# 16_LMS2_RF2_Misc.net
KiCad netlist of a schematic drawn in Altium Designer
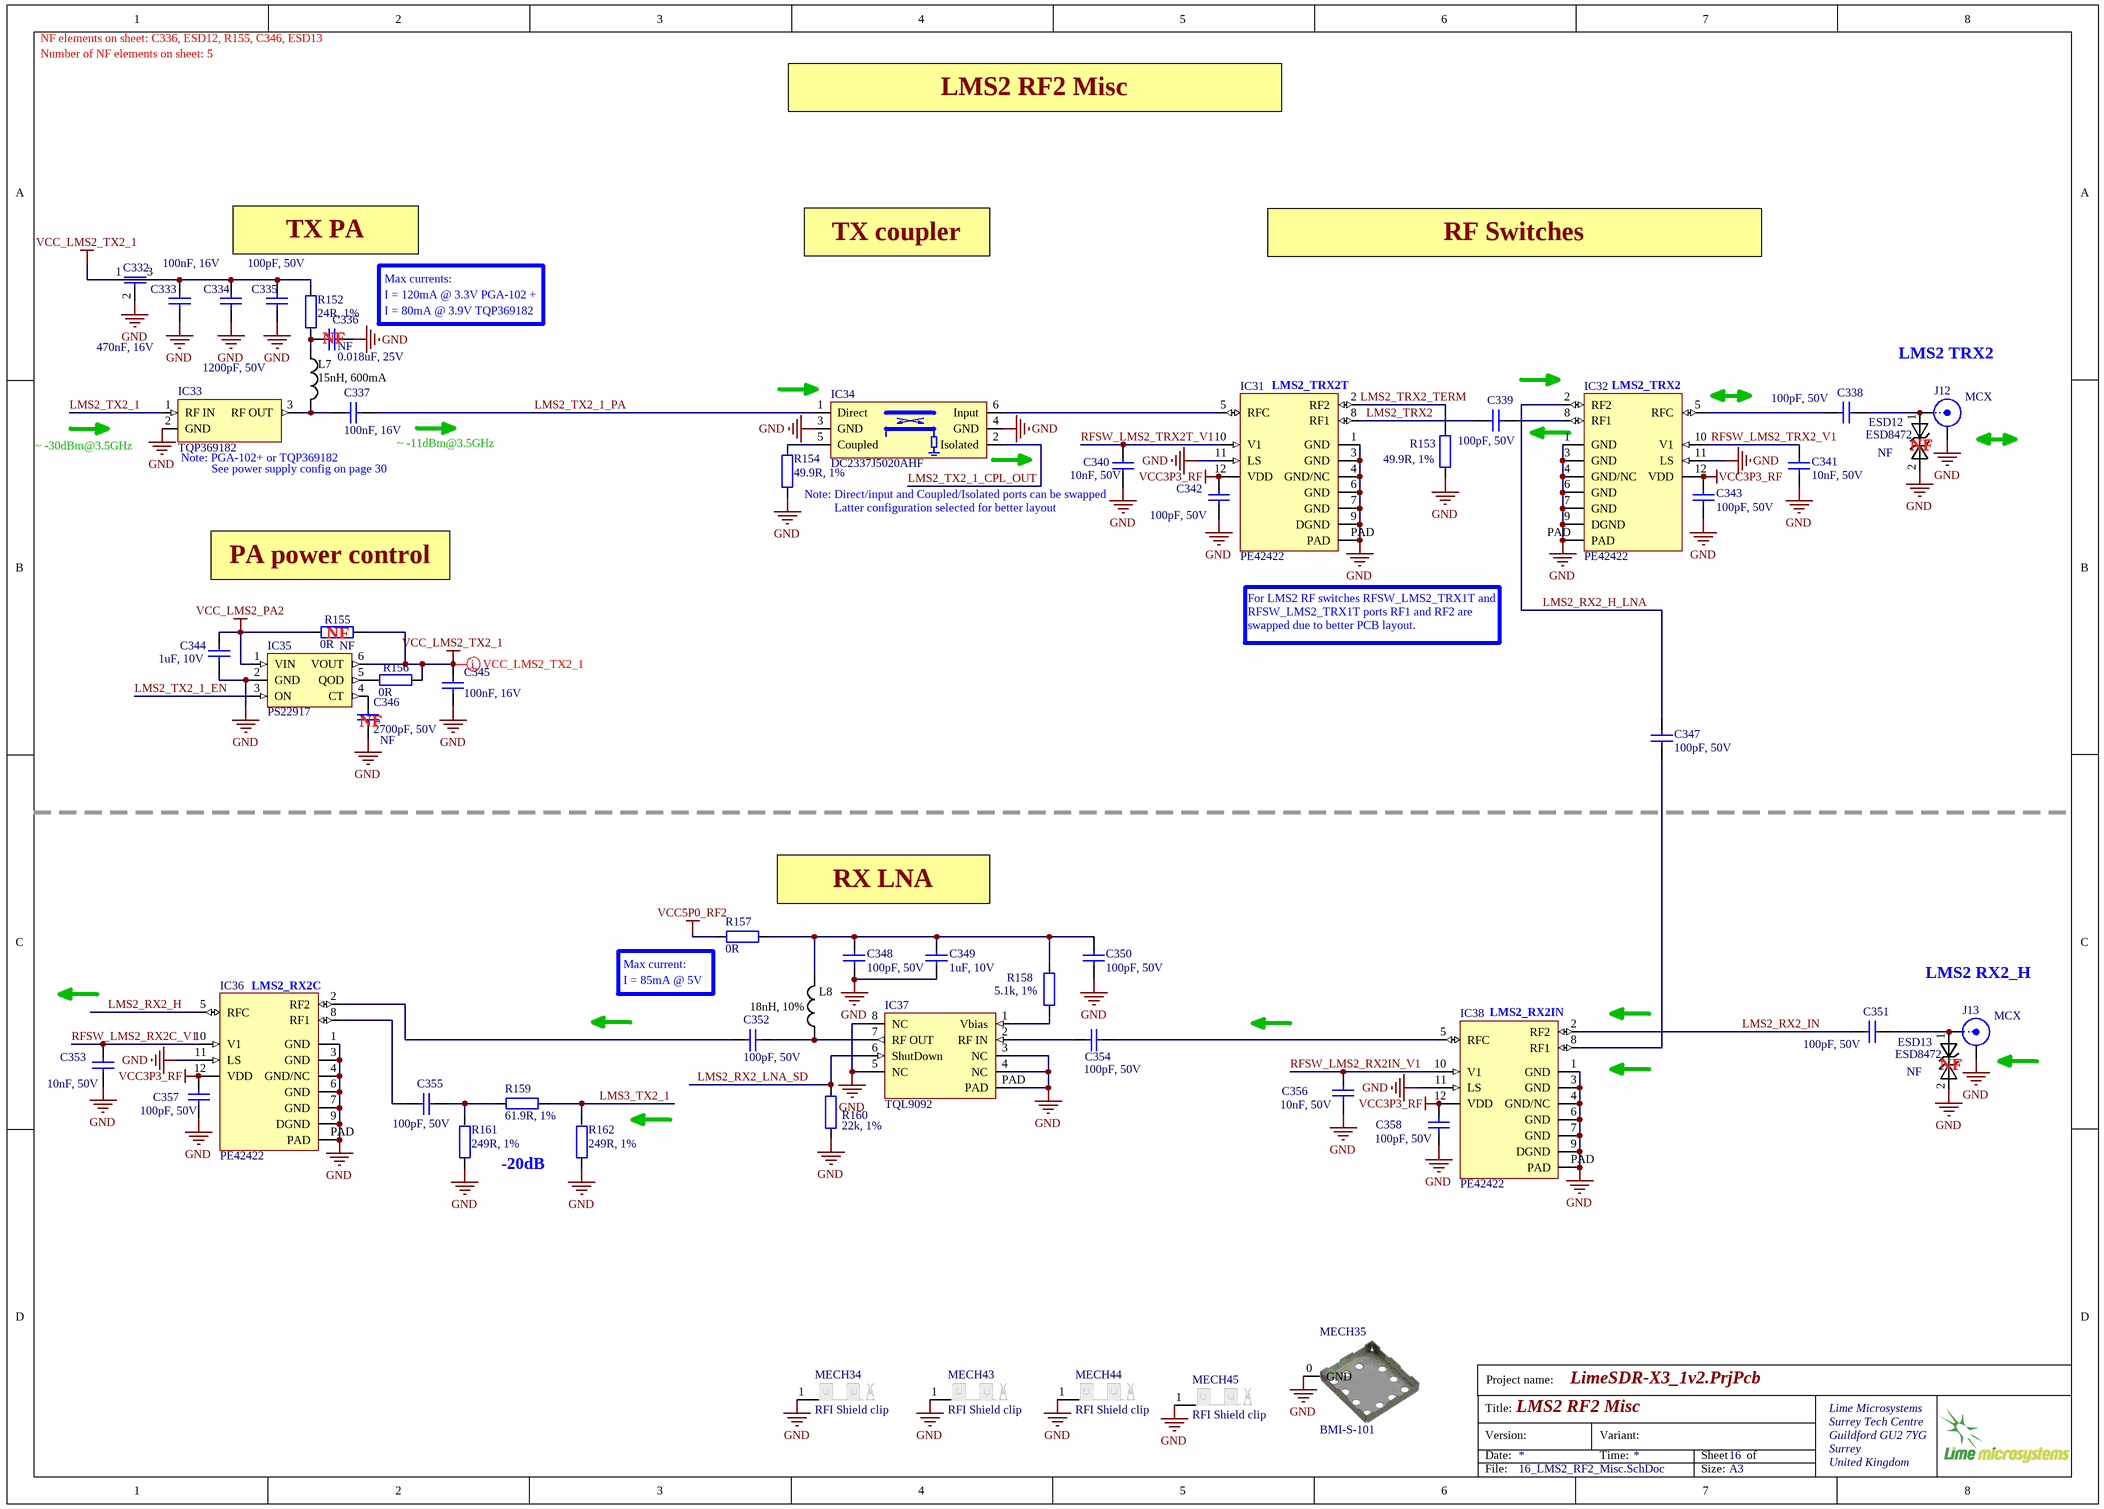
[diagram p0: 16_LMS2_RF2_Misc.SchDoc]

(export (version "E")
  (design (tool "Eeschema 10.0.6"))
  (components
    (comp (ref "C332")
      (value "470nF, 16V")
      (footprint "CAP0805_FEEDTHROUGH")
      (fields
        (field (name "MANUFACTURER") "Murata")
        (field (name "TOLERANCE") "20%")
        (field (name "VOLTAGE") "16V")
      )
      (libsource (lib "LimeMicroAltiumLib_schLib_r01") (part "Cap_feed_through"))
    )
    (comp (ref "C333")
      (value "100nF, 16V")
      (footprint "CAP0402")
      (fields (field (name "MANUFACTURER") "Murata Electronics") (field (name "TOLERANCE") "10 %"))
      (libsource (lib "") (part "Cap_0402_7"))
    )
    (comp (ref "C334")
      (value "1200pF, 50V")
      (footprint "CAP0402")
      (fields (field (name "MANUFACTURER") "Kemet") (field (name "TOLERANCE") "±5%"))
      (libsource (lib "") (part "Cap_0402_4"))
    )
    (comp (ref "C335")
      (value "100pF, 50V")
      (footprint "CAP0402")
      (fields (field (name "TOLERANCE") "±5%") (field (name "MANUFACTURER") "Yageo"))
      (libsource (lib "") (part "Cap_0402_7"))
    )
    (comp (ref "C336")
      (value "0.018uF, 25V")
      (footprint "CAP0402")
      (fields
        (field (name "ASSEMBLY INFO") "NF")
        (field (name "MANUFACTURER") "Yageo")
        (field (name "TOLERANCE") "10%")
      )
      (libsource (lib "") (part "Cap_0402_3"))
    )
    (comp (ref "C337")
      (value "100nF, 16V")
      (footprint "CAP0402")
      (fields (field (name "MANUFACTURER") "Murata Electronics") (field (name "TOLERANCE") "10 %"))
      (libsource (lib "") (part "Cap_0402_2"))
    )
    (comp (ref "C338")
      (value "100pF, 50V")
      (footprint "CAP0402")
      (fields (field (name "TOLERANCE") "±5%") (field (name "MANUFACTURER") "Yageo"))
      (libsource (lib "LimeMicroAltiumLib_schLib") (part "Cap_0402"))
    )
    (comp (ref "C339")
      (value "100pF, 50V")
      (footprint "CAP0402")
      (fields (field (name "TOLERANCE") "±5%") (field (name "MANUFACTURER") "Yageo"))
      (libsource (lib "LimeMicroAltiumLib_schLib") (part "Cap_0402"))
    )
    (comp (ref "C340")
      (value "10nF, 50V")
      (footprint "CAP0402")
      (fields
        (field (name "MANUFACTURER") "Murata Electronics North America")
        (field (name "TOLERANCE") "±10%")
      )
      (libsource (lib "") (part "Cap_0402_5"))
    )
    (comp (ref "C341")
      (value "10nF, 50V")
      (footprint "CAP0402")
      (fields
        (field (name "MANUFACTURER") "Murata Electronics North America")
        (field (name "TOLERANCE") "±10%")
      )
      (libsource (lib "") (part "Cap_0402_5"))
    )
    (comp (ref "C342")
      (value "100pF, 50V")
      (footprint "CAP0402")
      (fields (field (name "TOLERANCE") "±5%") (field (name "MANUFACTURER") "Yageo"))
      (libsource (lib "") (part "Cap_0402_10"))
    )
    (comp (ref "C343")
      (value "100pF, 50V")
      (footprint "CAP0402")
      (fields (field (name "TOLERANCE") "±5%") (field (name "MANUFACTURER") "Yageo"))
      (libsource (lib "") (part "Cap_0402_10"))
    )
    (comp (ref "C344")
      (value "1uF, 10V")
      (footprint "CAP0402")
      (fields (field (name "MANUFACTURER") "TDK"))
      (libsource (lib "") (part "Cap_0402_6"))
    )
    (comp (ref "C345")
      (value "100nF, 16V")
      (footprint "CAP0402")
      (fields (field (name "MANUFACTURER") "Murata Electronics") (field (name "TOLERANCE") "10 %"))
      (libsource (lib "") (part "Cap_0402_6"))
    )
    (comp (ref "C346")
      (value "2700pF, 50V")
      (footprint "CAP0402")
      (fields
        (field (name "ASSEMBLY INFO") "NF")
        (field (name "TOLERANCE") "±10%")
        (field (name "MANUFACTURER") "Murata Electronics North America")
      )
      (libsource (lib "") (part "Cap_0402_7"))
    )
    (comp (ref "C347")
      (value "100pF, 50V")
      (footprint "CAP0402")
      (fields (field (name "TOLERANCE") "±5%") (field (name "MANUFACTURER") "Yageo"))
      (libsource (lib "LimeMicroAltiumLib_schLib") (part "Cap_0402"))
    )
    (comp (ref "C348")
      (value "100pF, 50V")
      (footprint "CAP0402")
      (fields (field (name "TOLERANCE") "±5%") (field (name "MANUFACTURER") "Yageo"))
      (libsource (lib "") (part "Cap_0402_1"))
    )
    (comp (ref "C349")
      (value "1uF, 10V")
      (footprint "CAP0402")
      (fields (field (name "MANUFACTURER") "TDK"))
      (libsource (lib "") (part "Cap_0402_9"))
    )
    (comp (ref "C350")
      (value "100pF, 50V")
      (footprint "CAP0402")
      (fields (field (name "TOLERANCE") "±5%") (field (name "MANUFACTURER") "Yageo"))
      (libsource (lib "") (part "Cap_0402_1"))
    )
    (comp (ref "C351")
      (value "100pF, 50V")
      (footprint "CAP0402")
      (fields (field (name "TOLERANCE") "±5%") (field (name "MANUFACTURER") "Yageo"))
      (libsource (lib "LimeMicroAltiumLib_schLib") (part "Cap_0402"))
    )
    (comp (ref "C352")
      (value "100pF, 50V")
      (footprint "CAP0402")
      (fields (field (name "TOLERANCE") "±5%") (field (name "MANUFACTURER") "Yageo"))
      (libsource (lib "") (part "Cap_0402_6"))
    )
    (comp (ref "C353")
      (value "10nF, 50V")
      (footprint "CAP0402")
      (fields
        (field (name "MANUFACTURER") "Murata Electronics North America")
        (field (name "TOLERANCE") "±10%")
      )
      (libsource (lib "") (part "Cap_0402_8"))
    )
    (comp (ref "C354")
      (value "100pF, 50V")
      (footprint "CAP0402")
      (fields (field (name "TOLERANCE") "±5%") (field (name "MANUFACTURER") "Yageo"))
      (libsource (lib "") (part "Cap_0402_12"))
    )
    (comp (ref "C355")
      (value "100pF, 50V")
      (footprint "CAP0402")
      (fields (field (name "TOLERANCE") "±5%") (field (name "MANUFACTURER") "Yageo"))
      (libsource (lib "LimeMicroAltiumLib_schLib") (part "Cap_0402"))
    )
    (comp (ref "C356")
      (value "10nF, 50V")
      (footprint "CAP0402")
      (fields
        (field (name "MANUFACTURER") "Murata Electronics North America")
        (field (name "TOLERANCE") "±10%")
      )
      (libsource (lib "") (part "Cap_0402_3"))
    )
    (comp (ref "C357")
      (value "100pF, 50V")
      (footprint "CAP0402")
      (fields (field (name "TOLERANCE") "±5%") (field (name "MANUFACTURER") "Yageo"))
      (libsource (lib "") (part "Cap_0402_11"))
    )
    (comp (ref "C358")
      (value "100pF, 50V")
      (footprint "CAP0402")
      (fields (field (name "TOLERANCE") "±5%") (field (name "MANUFACTURER") "Yageo"))
      (libsource (lib "") (part "Cap_0402_2"))
    )
    (comp (ref "ESD12")
      (value "ESD8472")
      (footprint "ESD8472_X3DFN2")
      (fields (field (name "MANUFACTURER") "ON Semiconductor") (field (name "ASSEMBLY INFO") "NF"))
      (libsource (lib "LimeMicroAltiumLib_schLib") (part "ESD8472"))
    )
    (comp (ref "ESD13")
      (value "ESD8472")
      (footprint "ESD8472_X3DFN2")
      (fields (field (name "MANUFACTURER") "ON Semiconductor") (field (name "ASSEMBLY INFO") "NF"))
      (libsource (lib "") (part "ESD8472_1"))
    )
    (comp (ref "IC31")
      (value "PE42422")
      (footprint "PE42422_QFN12")
      (fields (field (name "MANUFACTURER") "Peregrine Semiconductor"))
      (libsource (lib "") (part "PE42422_2"))
    )
    (comp (ref "IC32")
      (value "PE42422")
      (footprint "PE42422_QFN12")
      (fields (field (name "MANUFACTURER") "Peregrine Semiconductor"))
      (libsource (lib "") (part "PE42422_3"))
    )
    (comp (ref "IC33")
      (value "TQP369182")
      (footprint "PGA-102+_SOT89")
      (fields (field (name "MANUFACTURER") "Qorvo"))
      (libsource (lib "LimeMicroAltiumLib_schLib_r01") (part "PGA-102+_PA"))
    )
    (comp (ref "IC34")
      (value "DC2337J5020AHF")
      (footprint "DC2337J5020AHF_ANAREN_COUPLER_0805")
      (fields (field (name "MANUFACTURER") "Anaren"))
      (libsource (lib "LimeMicroAltiumLib_schLib_r02") (part "DC2337J5020AHF_coupler"))
    )
    (comp (ref "IC35")
      (value "PS22917")
      (footprint "SOT23-6")
      (fields (field (name "MANUFACTURER") "Texas Instruments"))
      (libsource (lib "LimeMicroAltiumLib_schLib") (part "TPS22918"))
    )
    (comp (ref "IC36")
      (value "PE42422")
      (footprint "PE42422_QFN12")
      (fields (field (name "MANUFACTURER") "Peregrine Semiconductor"))
      (libsource (lib "LimeMicroAltiumLib_schLib") (part "PE42422"))
    )
    (comp (ref "IC37")
      (value "TQL9092")
      (footprint "TQL9092")
      (fields (field (name "MANUFACTURER") "Qorvo"))
      (libsource (lib "LimeMicroAltiumLib_schLib") (part "TQL9092"))
    )
    (comp (ref "IC38")
      (value "PE42422")
      (footprint "PE42422_QFN12")
      (fields (field (name "MANUFACTURER") "Peregrine Semiconductor"))
      (libsource (lib "") (part "PE42422_1"))
    )
    (comp (ref "J12")
      (value "MCX")
      (footprint "MCX_connector_vertical_SM")
      (fields (field (name "MANUFACTURER") "Bel Cinch"))
      (libsource (lib "LimeMicroAltiumLib_schLib") (part "RF_IF_connector"))
    )
    (comp (ref "J13")
      (value "MCX")
      (footprint "MCX_connector_vertical_SM")
      (fields (field (name "MANUFACTURER") "Bel Cinch"))
      (libsource (lib "LimeMicroAltiumLib_schLib") (part "RF_IF_connector"))
    )
    (comp (ref "L7")
      (value "15nH, 600mA")
      (footprint "RES0805")
      (fields (field (name "MANUFACTURER") "Bourns") (field (name "TOLERANCE") "5%"))
      (libsource (lib "LimeMicroAltiumLib_schLib") (part "Inductor_0603"))
    )
    (comp (ref "L8")
      (value "18nH, 10%")
      (footprint "RES0603")
      (fields (field (name "MANUFACTURER") "Pulse Electronics Network") (field (name "TOLERANCE") "±10%"))
      (libsource (lib "LimeMicroAltiumLib_schLib") (part "Inductor"))
    )
    (comp (ref "MECH34")
      (value "RFI Shield clip")
      (footprint "RFI_SHIELD_CLPS_MINI")
      (fields (field (name "MANUFACTURER") "HARWIN"))
      (libsource (lib "LimeMicroAltiumLib") (part "RFI_SHIELD_CLIP"))
    )
    (comp (ref "MECH35")
      (value "BMI-S-101")
      (footprint "BMI-S-101_RF_SHIELD_v2")
      (fields (field (name "MANUFACTURER") "Laird"))
      (libsource (lib "LimeMicroAltiumLib") (part "BMI-S-101_RF_SHIELD"))
    )
    (comp (ref "MECH43")
      (value "RFI Shield clip")
      (footprint "RFI_SHIELD_CLPS_MINI")
      (fields (field (name "MANUFACTURER") "HARWIN"))
      (libsource (lib "LimeMicroAltiumLib") (part "RFI_SHIELD_CLIP"))
    )
    (comp (ref "MECH44")
      (value "RFI Shield clip")
      (footprint "RFI_SHIELD_CLPS_MINI")
      (fields (field (name "MANUFACTURER") "HARWIN"))
      (libsource (lib "LimeMicroAltiumLib") (part "RFI_SHIELD_CLIP"))
    )
    (comp (ref "MECH45")
      (value "RFI Shield clip")
      (footprint "RFI_SHIELD_CLPS_MINI")
      (fields (field (name "MANUFACTURER") "HARWIN"))
      (libsource (lib "LimeMicroAltiumLib") (part "RFI_SHIELD_CLIP"))
    )
    (comp (ref "R152")
      (value "24R, 1%")
      (footprint "RES0402")
      (fields (field (name "MANUFACTURER") "Yageo") (field (name "TOLERANCE") "1%"))
      (libsource (lib "LimeFPGAboard_schLib") (part "Res_0402"))
    )
    (comp (ref "R153")
      (value "49.9R, 1%")
      (footprint "RES0402")
      (fields
        (field (name "TOLERANCE") "±1%")
        (field (name "MANUFACTURER") "Samsung Electro-Mechanics America, Inc.")
        (field (name "MANUFACTURER PART NUMBER") "RC1005F49R9CS")
      )
      (libsource (lib "") (part "Res_0402_1"))
    )
    (comp (ref "R154")
      (value "49.9R, 1%")
      (footprint "RES0402")
      (fields
        (field (name "TOLERANCE") "±1%")
        (field (name "MANUFACTURER") "Samsung Electro-Mechanics America, Inc.")
        (field (name "MANUFACTURER PART NUMBER") "RC1005F49R9CS")
      )
      (libsource (lib "") (part "Res_0402_1"))
    )
    (comp (ref "R155")
      (value "0R")
      (footprint "RES0402")
      (fields
        (field (name "ASSEMBLY INFO") "NF")
        (field (name "MANUFACTURER") "Yageo")
        (field (name "TOLERANCE") "Jumper")
      )
      (libsource (lib "LimeMicroAltiumLib_schLib") (part "Res_0402"))
    )
    (comp (ref "R156")
      (value "0R")
      (footprint "RES0402")
      (fields (field (name "MANUFACTURER") "Yageo") (field (name "TOLERANCE") "Jumper"))
      (libsource (lib "LimeMicroAltiumLib_schLib") (part "Res_0402"))
    )
    (comp (ref "R157")
      (value "0R")
      (footprint "RES0402")
      (fields (field (name "MANUFACTURER") "Yageo") (field (name "TOLERANCE") "Jumper"))
      (libsource (lib "") (part "Res_0402_1"))
    )
    (comp (ref "R158")
      (value "5.1k, 1%")
      (footprint "RES0603")
      (fields (field (name "MANUFACTURER") "Stackpole Electronics") (field (name "TOLERANCE") "1%"))
      (libsource (lib "LimeMicroAltiumLib_schLib") (part "Res_0603"))
    )
    (comp (ref "R159")
      (value "61.9R, 1%")
      (footprint "RES0402")
      (fields (field (name "MANUFACTURER") "Yageo") (field (name "TOLERANCE") "1%"))
      (libsource (lib "LimeMicroAltiumLib_schLib") (part "Res_0402"))
    )
    (comp (ref "R160")
      (value "22k, 1%")
      (footprint "RES0402")
      (fields (field (name "MANUFACTURER") "Yageo") (field (name "TOLERANCE") "±1%"))
      (libsource (lib "LimeMicroAltiumLib_schLib") (part "Res_0402"))
    )
    (comp (ref "R161")
      (value "249R, 1%")
      (footprint "RES0402")
      (fields (field (name "MANUFACTURER") "Stackpole Electronics Inc") (field (name "TOLERANCE") "±1%"))
      (libsource (lib "LimeMicroAltiumLib_schLib") (part "Res_0402"))
    )
    (comp (ref "R162")
      (value "249R, 1%")
      (footprint "RES0402")
      (fields (field (name "MANUFACTURER") "Stackpole Electronics Inc") (field (name "TOLERANCE") "±1%"))
      (libsource (lib "LimeMicroAltiumLib_schLib") (part "Res_0402"))
    )
  )
  (nets
    (net (code "1") (name "/LMS2_RX2_H") (class "Default")
      (node (ref "IC36") (pin "5") (pinfunction "RFC_5") (pintype "bidirectional"))
    )
    (net (code "2") (name "/LMS2_RX2_H_LNA") (class "Default")
      (node (ref "C347") (pin "2") (pinfunction "2_2") (pintype "passive"))
      (node (ref "IC32") (pin "2") (pinfunction "RF2_2") (pintype "bidirectional"))
    )
    (net (code "3") (name "/LMS2_RX2_IN") (class "Default")
      (node (ref "C351") (pin "1") (pinfunction "1_1") (pintype "passive"))
      (node (ref "IC38") (pin "2") (pinfunction "RF2_2") (pintype "bidirectional"))
    )
    (net (code "4") (name "/LMS2_RX2_LNA_SD") (class "Default")
      (node (ref "IC37") (pin "6") (pinfunction "ShutDown_6") (pintype "input"))
      (node (ref "R160") (pin "2") (pinfunction "2_2") (pintype "passive"))
    )
    (net (code "5") (name "/LMS2_TRX2") (class "Default")
      (node (ref "C339") (pin "1") (pinfunction "1_1") (pintype "passive"))
      (node (ref "IC31") (pin "8") (pinfunction "RF1_8") (pintype "bidirectional"))
    )
    (net (code "6") (name "/LMS2_TRX2_TERM") (class "Default")
      (node (ref "IC31") (pin "2") (pinfunction "RF2_2") (pintype "bidirectional"))
      (node (ref "R153") (pin "1") (pinfunction "1_1") (pintype "passive"))
    )
    (net (code "7") (name "/LMS2_TX2_1") (class "Default")
      (node (ref "IC33") (pin "1") (pinfunction "RF_IN_1") (pintype "input"))
    )
    (net (code "8") (name "/LMS2_TX2_1_CPL_OUT") (class "Default")
      (node (ref "IC34") (pin "2") (pinfunction "Isolated_2") (pintype "passive"))
    )
    (net (code "9") (name "/LMS2_TX2_1_EN") (class "Default")
      (node (ref "IC35") (pin "3") (pinfunction "ON_3") (pintype "input"))
    )
    (net (code "10") (name "/LMS2_TX2_1_PA") (class "Default")
      (node (ref "C337") (pin "1") (pinfunction "1_1") (pintype "passive"))
      (node (ref "IC34") (pin "1") (pinfunction "Direct_1") (pintype "passive"))
    )
    (net (code "11") (name "/LMS3_TX2_1") (class "Default")
      (node (ref "R159") (pin "2") (pinfunction "2_2") (pintype "passive"))
      (node (ref "R162") (pin "2") (pinfunction "2_2") (pintype "passive"))
    )
    (net (code "12") (name "/RFSW_LMS2_RX2C_V1") (class "Default")
      (node (ref "C353") (pin "1") (pinfunction "1_1") (pintype "passive"))
      (node (ref "IC36") (pin "10") (pinfunction "V1_10") (pintype "input"))
    )
    (net (code "13") (name "/RFSW_LMS2_RX2IN_V1") (class "Default")
      (node (ref "C356") (pin "1") (pinfunction "1_1") (pintype "passive"))
      (node (ref "IC38") (pin "10") (pinfunction "V1_10") (pintype "input"))
    )
    (net (code "14") (name "/RFSW_LMS2_TRX2T_V1") (class "Default")
      (node (ref "C340") (pin "1") (pinfunction "1_1") (pintype "passive"))
      (node (ref "IC31") (pin "10") (pinfunction "V1_10") (pintype "input"))
    )
    (net (code "15") (name "/RFSW_LMS2_TRX2_V1") (class "Default")
      (node (ref "C341") (pin "1") (pinfunction "1_1") (pintype "passive"))
      (node (ref "IC32") (pin "10") (pinfunction "V1_10") (pintype "input"))
    )
    (net (code "16") (name "GND") (class "Default")
      (node (ref "C332") (pin "2") (pinfunction "2_2") (pintype "passive"))
      (node (ref "C333") (pin "1") (pinfunction "1_1") (pintype "passive"))
      (node (ref "C334") (pin "2") (pinfunction "2_2") (pintype "passive"))
      (node (ref "C335") (pin "2") (pinfunction "2_2") (pintype "passive"))
      (node (ref "C336") (pin "2") (pinfunction "2_2") (pintype "passive"))
      (node (ref "C340") (pin "2") (pinfunction "2_2") (pintype "passive"))
      (node (ref "C341") (pin "2") (pinfunction "2_2") (pintype "passive"))
      (node (ref "C342") (pin "1") (pinfunction "1_1") (pintype "passive"))
      (node (ref "C343") (pin "1") (pinfunction "1_1") (pintype "passive"))
      (node (ref "C344") (pin "1") (pinfunction "1_1") (pintype "passive"))
      (node (ref "C345") (pin "1") (pinfunction "1_1") (pintype "passive"))
      (node (ref "C346") (pin "2") (pinfunction "2_2") (pintype "passive"))
      (node (ref "C348") (pin "2") (pinfunction "2_2") (pintype "passive"))
      (node (ref "C349") (pin "1") (pinfunction "1_1") (pintype "passive"))
      (node (ref "C350") (pin "2") (pinfunction "2_2") (pintype "passive"))
      (node (ref "C353") (pin "2") (pinfunction "2_2") (pintype "passive"))
      (node (ref "C356") (pin "2") (pinfunction "2_2") (pintype "passive"))
      (node (ref "C357") (pin "1") (pinfunction "1_1") (pintype "passive"))
      (node (ref "C358") (pin "1") (pinfunction "1_1") (pintype "passive"))
      (node (ref "ESD12") (pin "2") (pinfunction "2_2") (pintype "passive"))
      (node (ref "ESD13") (pin "2") (pinfunction "2_2") (pintype "passive"))
      (node (ref "IC31") (pin "1") (pinfunction "GND_1") (pintype "passive"))
      (node (ref "IC31") (pin "11") (pinfunction "LS_11") (pintype "input"))
      (node (ref "IC31") (pin "3") (pinfunction "GND_3") (pintype "passive"))
      (node (ref "IC31") (pin "4") (pinfunction "GND/NC_4") (pintype "passive"))
      (node (ref "IC31") (pin "6") (pinfunction "GND_6") (pintype "passive"))
      (node (ref "IC31") (pin "7") (pinfunction "GND_7") (pintype "passive"))
      (node (ref "IC31") (pin "9") (pinfunction "DGND_9") (pintype "passive"))
      (node (ref "IC31") (pin "PAD") (pinfunction "PAD_PAD") (pintype "passive"))
      (node (ref "IC32") (pin "1") (pinfunction "GND_1") (pintype "passive"))
      (node (ref "IC32") (pin "11") (pinfunction "LS_11") (pintype "input"))
      (node (ref "IC32") (pin "3") (pinfunction "GND_3") (pintype "passive"))
      (node (ref "IC32") (pin "4") (pinfunction "GND/NC_4") (pintype "passive"))
      (node (ref "IC32") (pin "6") (pinfunction "GND_6") (pintype "passive"))
      (node (ref "IC32") (pin "7") (pinfunction "GND_7") (pintype "passive"))
      (node (ref "IC32") (pin "9") (pinfunction "DGND_9") (pintype "passive"))
      (node (ref "IC32") (pin "PAD") (pinfunction "PAD_PAD") (pintype "passive"))
      (node (ref "IC33") (pin "2") (pinfunction "GND_2") (pintype "passive"))
      (node (ref "IC34") (pin "3") (pinfunction "GND_3") (pintype "passive"))
      (node (ref "IC34") (pin "4") (pinfunction "GND_4") (pintype "passive"))
      (node (ref "IC35") (pin "2") (pinfunction "GND_2") (pintype "passive"))
      (node (ref "IC36") (pin "1") (pinfunction "GND_1") (pintype "passive"))
      (node (ref "IC36") (pin "11") (pinfunction "LS_11") (pintype "input"))
      (node (ref "IC36") (pin "3") (pinfunction "GND_3") (pintype "passive"))
      (node (ref "IC36") (pin "4") (pinfunction "GND/NC_4") (pintype "passive"))
      (node (ref "IC36") (pin "6") (pinfunction "GND_6") (pintype "passive"))
      (node (ref "IC36") (pin "7") (pinfunction "GND_7") (pintype "passive"))
      (node (ref "IC36") (pin "9") (pinfunction "DGND_9") (pintype "passive"))
      (node (ref "IC36") (pin "PAD") (pinfunction "PAD_PAD") (pintype "passive"))
      (node (ref "IC37") (pin "3") (pinfunction "NC_3") (pintype "passive"))
      (node (ref "IC37") (pin "4") (pinfunction "NC_4") (pintype "passive"))
      (node (ref "IC37") (pin "5") (pinfunction "NC_5") (pintype "passive"))
      (node (ref "IC37") (pin "8") (pinfunction "NC_8") (pintype "passive"))
      (node (ref "IC37") (pin "PAD") (pinfunction "PAD_PAD") (pintype "passive"))
      (node (ref "IC38") (pin "1") (pinfunction "GND_1") (pintype "passive"))
      (node (ref "IC38") (pin "11") (pinfunction "LS_11") (pintype "input"))
      (node (ref "IC38") (pin "3") (pinfunction "GND_3") (pintype "passive"))
      (node (ref "IC38") (pin "4") (pinfunction "GND/NC_4") (pintype "passive"))
      (node (ref "IC38") (pin "6") (pinfunction "GND_6") (pintype "passive"))
      (node (ref "IC38") (pin "7") (pinfunction "GND_7") (pintype "passive"))
      (node (ref "IC38") (pin "9") (pinfunction "DGND_9") (pintype "passive"))
      (node (ref "IC38") (pin "PAD") (pinfunction "PAD_PAD") (pintype "passive"))
      (node (ref "J12") (pin "2") (pinfunction "Y_2") (pintype "passive"))
      (node (ref "J13") (pin "2") (pinfunction "Y_2") (pintype "passive"))
      (node (ref "MECH34") (pin "1") (pinfunction "GND_1") (pintype "passive"))
      (node (ref "MECH35") (pin "0") (pinfunction "GND_0") (pintype "passive"))
      (node (ref "MECH43") (pin "1") (pinfunction "GND_1") (pintype "passive"))
      (node (ref "MECH44") (pin "1") (pinfunction "GND_1") (pintype "passive"))
      (node (ref "MECH45") (pin "1") (pinfunction "GND_1") (pintype "passive"))
      (node (ref "R153") (pin "2") (pinfunction "2_2") (pintype "passive"))
      (node (ref "R154") (pin "2") (pinfunction "2_2") (pintype "passive"))
      (node (ref "R160") (pin "1") (pinfunction "1_1") (pintype "passive"))
      (node (ref "R161") (pin "1") (pinfunction "1_1") (pintype "passive"))
      (node (ref "R162") (pin "1") (pinfunction "1_1") (pintype "passive"))
    )
    (net (code "17") (name "Net-(C332-Pad3)") (class "Default")
      (node (ref "C332") (pin "3") (pinfunction "3_3") (pintype "passive"))
      (node (ref "C333") (pin "2") (pinfunction "2_2") (pintype "passive"))
      (node (ref "C334") (pin "1") (pinfunction "1_1") (pintype "passive"))
      (node (ref "C335") (pin "1") (pinfunction "1_1") (pintype "passive"))
      (node (ref "R152") (pin "1") (pinfunction "1_1") (pintype "passive"))
    )
    (net (code "18") (name "Net-(C336-Pad1)") (class "Default")
      (node (ref "C336") (pin "1") (pinfunction "1_1") (pintype "passive"))
      (node (ref "L7") (pin "1") (pinfunction "1_1") (pintype "passive"))
      (node (ref "R152") (pin "2") (pinfunction "2_2") (pintype "passive"))
    )
    (net (code "19") (name "Net-(C348-Pad1)") (class "Default")
      (node (ref "C348") (pin "1") (pinfunction "1_1") (pintype "passive"))
      (node (ref "C349") (pin "2") (pinfunction "2_2") (pintype "passive"))
      (node (ref "C350") (pin "1") (pinfunction "1_1") (pintype "passive"))
      (node (ref "L8") (pin "1") (pinfunction "1_1") (pintype "passive"))
      (node (ref "R157") (pin "2") (pinfunction "2_2") (pintype "passive"))
      (node (ref "R158") (pin "2") (pinfunction "2_2") (pintype "passive"))
    )
    (net (code "20") (name "Net-(C355-Pad1)") (class "Default")
      (node (ref "C355") (pin "1") (pinfunction "1_1") (pintype "passive"))
      (node (ref "R159") (pin "1") (pinfunction "1_1") (pintype "passive"))
      (node (ref "R161") (pin "2") (pinfunction "2_2") (pintype "passive"))
    )
    (net (code "21") (name "Net-(IC31-RFC)") (class "Default")
      (node (ref "IC31") (pin "5") (pinfunction "RFC_5") (pintype "bidirectional"))
      (node (ref "IC34") (pin "6") (pinfunction "Input_6") (pintype "passive"))
    )
    (net (code "22") (name "Net-(IC32-RF1)") (class "Default")
      (node (ref "C339") (pin "2") (pinfunction "2_2") (pintype "passive"))
      (node (ref "IC32") (pin "8") (pinfunction "RF1_8") (pintype "bidirectional"))
    )
    (net (code "23") (name "Net-(IC32-RFC)") (class "Default")
      (node (ref "C338") (pin "1") (pinfunction "1_1") (pintype "passive"))
      (node (ref "IC32") (pin "5") (pinfunction "RFC_5") (pintype "bidirectional"))
    )
    (net (code "24") (name "Net-(IC33-RF_OUT)") (class "Default")
      (node (ref "C337") (pin "2") (pinfunction "2_2") (pintype "passive"))
      (node (ref "IC33") (pin "3") (pinfunction "RF_OUT_3") (pintype "output"))
      (node (ref "L7") (pin "2") (pinfunction "2_2") (pintype "passive"))
    )
    (net (code "25") (name "Net-(IC34-Coupled)") (class "Default")
      (node (ref "IC34") (pin "5") (pinfunction "Coupled_5") (pintype "passive"))
      (node (ref "R154") (pin "1") (pinfunction "1_1") (pintype "passive"))
    )
    (net (code "26") (name "Net-(IC35-CT)") (class "Default")
      (node (ref "C346") (pin "1") (pinfunction "1_1") (pintype "passive"))
      (node (ref "IC35") (pin "4") (pinfunction "CT_4") (pintype "output"))
    )
    (net (code "27") (name "Net-(IC35-QOD)") (class "Default")
      (node (ref "IC35") (pin "5") (pinfunction "QOD_5") (pintype "output"))
      (node (ref "R156") (pin "2") (pinfunction "2_2") (pintype "passive"))
    )
    (net (code "28") (name "Net-(IC36-RF1)") (class "Default")
      (node (ref "C355") (pin "2") (pinfunction "2_2") (pintype "passive"))
      (node (ref "IC36") (pin "8") (pinfunction "RF1_8") (pintype "bidirectional"))
    )
    (net (code "29") (name "Net-(IC36-RF2)") (class "Default")
      (node (ref "C352") (pin "1") (pinfunction "1_1") (pintype "passive"))
      (node (ref "IC36") (pin "2") (pinfunction "RF2_2") (pintype "bidirectional"))
    )
    (net (code "30") (name "Net-(IC37-RF_IN)") (class "Default")
      (node (ref "C354") (pin "1") (pinfunction "1_1") (pintype "passive"))
      (node (ref "IC37") (pin "2") (pinfunction "RF_IN_2") (pintype "input"))
    )
    (net (code "31") (name "Net-(IC37-RF_OUT)") (class "Default")
      (node (ref "C352") (pin "2") (pinfunction "2_2") (pintype "passive"))
      (node (ref "IC37") (pin "7") (pinfunction "RF_OUT_7") (pintype "output"))
      (node (ref "L8") (pin "2") (pinfunction "2_2") (pintype "passive"))
    )
    (net (code "32") (name "Net-(IC37-Vbias)") (class "Default")
      (node (ref "IC37") (pin "1") (pinfunction "Vbias_1") (pintype "input"))
      (node (ref "R158") (pin "1") (pinfunction "1_1") (pintype "passive"))
    )
    (net (code "33") (name "Net-(IC38-RF1)") (class "Default")
      (node (ref "C347") (pin "1") (pinfunction "1_1") (pintype "passive"))
      (node (ref "IC38") (pin "8") (pinfunction "RF1_8") (pintype "bidirectional"))
    )
    (net (code "34") (name "Net-(IC38-RFC)") (class "Default")
      (node (ref "C354") (pin "2") (pinfunction "2_2") (pintype "passive"))
      (node (ref "IC38") (pin "5") (pinfunction "RFC_5") (pintype "bidirectional"))
    )
    (net (code "35") (name "Net-(J12-X)") (class "Default")
      (node (ref "C338") (pin "2") (pinfunction "2_2") (pintype "passive"))
      (node (ref "ESD12") (pin "1") (pinfunction "1_1") (pintype "passive"))
      (node (ref "J12") (pin "1") (pinfunction "X_1") (pintype "passive"))
    )
    (net (code "36") (name "Net-(J13-X)") (class "Default")
      (node (ref "C351") (pin "2") (pinfunction "2_2") (pintype "passive"))
      (node (ref "ESD13") (pin "1") (pinfunction "1_1") (pintype "passive"))
      (node (ref "J13") (pin "1") (pinfunction "X_1") (pintype "passive"))
    )
    (net (code "37") (name "VCC3P3_RF") (class "Default")
      (node (ref "C342") (pin "2") (pinfunction "2_2") (pintype "passive"))
      (node (ref "C343") (pin "2") (pinfunction "2_2") (pintype "passive"))
      (node (ref "C357") (pin "2") (pinfunction "2_2") (pintype "passive"))
      (node (ref "C358") (pin "2") (pinfunction "2_2") (pintype "passive"))
      (node (ref "IC31") (pin "12") (pinfunction "VDD_12") (pintype "power_in"))
      (node (ref "IC32") (pin "12") (pinfunction "VDD_12") (pintype "power_in"))
      (node (ref "IC36") (pin "12") (pinfunction "VDD_12") (pintype "power_in"))
      (node (ref "IC38") (pin "12") (pinfunction "VDD_12") (pintype "power_in"))
    )
    (net (code "38") (name "VCC5P0_RF2") (class "Default")
      (node (ref "R157") (pin "1") (pinfunction "1_1") (pintype "passive"))
    )
    (net (code "39") (name "VCC_LMS2_PA2") (class "Default")
      (node (ref "C344") (pin "2") (pinfunction "2_2") (pintype "passive"))
      (node (ref "IC35") (pin "1") (pinfunction "VIN_1") (pintype "input"))
      (node (ref "R155") (pin "2") (pinfunction "2_2") (pintype "passive"))
    )
    (net (code "40") (name "VCC_LMS2_TX2_1") (class "Default")
      (node (ref "C332") (pin "1") (pinfunction "1_1") (pintype "passive"))
      (node (ref "C345") (pin "2") (pinfunction "2_2") (pintype "passive"))
      (node (ref "IC35") (pin "6") (pinfunction "VOUT_6") (pintype "output"))
      (node (ref "R155") (pin "1") (pinfunction "1_1") (pintype "passive"))
      (node (ref "R156") (pin "1") (pinfunction "1_1") (pintype "passive"))
    )
  )
)
